# Main.net
KiCad netlist of a schematic drawn in Altium Designer
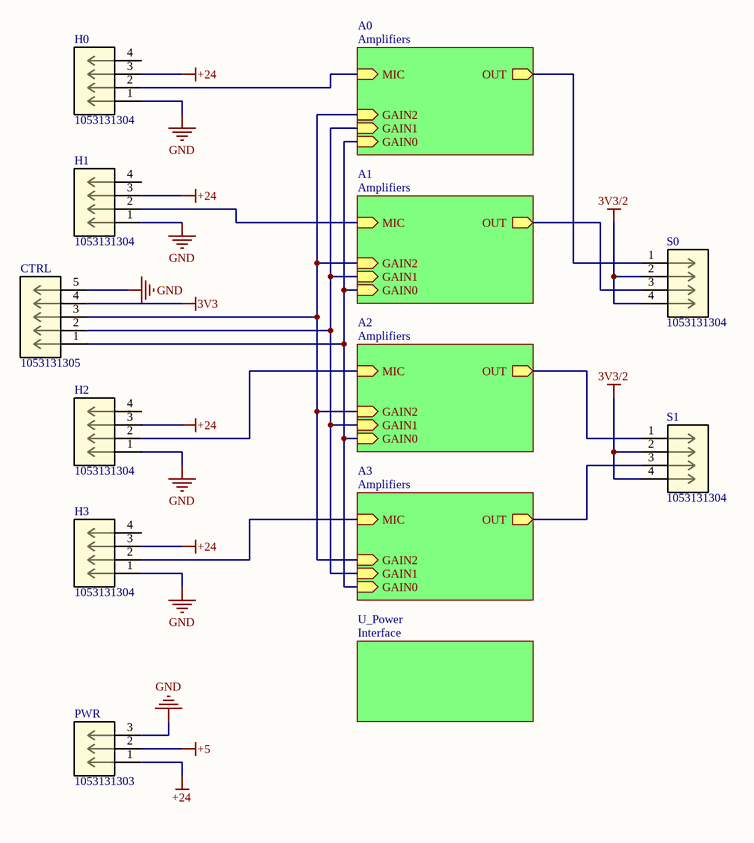
[diagram p0: Main.SchDoc]

(export (version "E")
  (design (tool "Eeschema 10.0.6"))
  (components
    (comp (ref "CTRL")
      (value "1053131305")
      (footprint "CON_1053131305")
      (description "No Description Available")
      (fields (field (name "COPYRIGHT") "Copyright (C) 2023 Ultra Librarian. All rights reserved."))
      (libsource (lib "1053131305") (part "1053131305"))
    )
    (comp (ref "H0")
      (value "1053131304")
      (footprint "CON_1053131304")
      (description "No Description Available")
      (fields (field (name "COPYRIGHT") "Copyright (C) 2023 Ultra Librarian. All rights reserved."))
      (libsource (lib "") (part "1053131304_1"))
    )
    (comp (ref "H1")
      (value "1053131304")
      (footprint "CON_1053131304")
      (description "No Description Available")
      (fields (field (name "COPYRIGHT") "Copyright (C) 2023 Ultra Librarian. All rights reserved."))
      (libsource (lib "") (part "1053131304_1"))
    )
    (comp (ref "H2")
      (value "1053131304")
      (footprint "CON_1053131304")
      (description "No Description Available")
      (fields (field (name "COPYRIGHT") "Copyright (C) 2023 Ultra Librarian. All rights reserved."))
      (libsource (lib "") (part "1053131304_1"))
    )
    (comp (ref "H3")
      (value "1053131304")
      (footprint "CON_1053131304")
      (description "No Description Available")
      (fields (field (name "COPYRIGHT") "Copyright (C) 2023 Ultra Librarian. All rights reserved."))
      (libsource (lib "") (part "1053131304_1"))
    )
    (comp (ref "PWR")
      (value "1053131303")
      (footprint "CON_1053131303")
      (description "No Description Available")
      (fields (field (name "COPYRIGHT") "Copyright (C) 2023 Ultra Librarian. All rights reserved."))
      (libsource (lib "1053131303") (part "1053131303"))
    )
    (comp (ref "S0")
      (value "1053131304")
      (footprint "CON_1053131304")
      (description "No Description Available")
      (fields (field (name "COPYRIGHT") "Copyright (C) 2023 Ultra Librarian. All rights reserved."))
      (libsource (lib "1053131304") (part "1053131304"))
    )
    (comp (ref "S1")
      (value "1053131304")
      (footprint "CON_1053131304")
      (description "No Description Available")
      (fields (field (name "COPYRIGHT") "Copyright (C) 2023 Ultra Librarian. All rights reserved."))
      (libsource (lib "1053131304") (part "1053131304"))
    )
  )
  (nets
    (net (code "1") (name "+5") (class "Default")
      (node (ref "PWR") (pin "2") (pinfunction "2_2") (pintype "passive"))
    )
    (net (code "2") (name "+24") (class "Default")
      (node (ref "H0") (pin "3") (pinfunction "3_3") (pintype "passive"))
      (node (ref "H1") (pin "3") (pinfunction "3_3") (pintype "passive"))
      (node (ref "H2") (pin "3") (pinfunction "3_3") (pintype "passive"))
      (node (ref "H3") (pin "3") (pinfunction "3_3") (pintype "passive"))
      (node (ref "PWR") (pin "1") (pinfunction "1_1") (pintype "passive"))
    )
    (net (code "3") (name "/GAIN0") (class "Default")
      (node (ref "CTRL") (pin "1") (pinfunction "1_1") (pintype "passive"))
    )
    (net (code "4") (name "/GAIN1") (class "Default")
      (node (ref "CTRL") (pin "2") (pinfunction "2_2") (pintype "passive"))
    )
    (net (code "5") (name "/GAIN2") (class "Default")
      (node (ref "CTRL") (pin "3") (pinfunction "3_3") (pintype "passive"))
    )
    (net (code "6") (name "/MIC") (class "Default")
      (node (ref "H2") (pin "2") (pinfunction "2_2") (pintype "passive"))
    )
    (net (code "7") (name "/MIC_1") (class "Default")
      (node (ref "H0") (pin "2") (pinfunction "2_2") (pintype "passive"))
    )
    (net (code "8") (name "/MIC_2") (class "Default")
      (node (ref "H1") (pin "2") (pinfunction "2_2") (pintype "passive"))
    )
    (net (code "9") (name "/MIC_3") (class "Default")
      (node (ref "H3") (pin "2") (pinfunction "2_2") (pintype "passive"))
    )
    (net (code "10") (name "/OUT") (class "Default")
      (node (ref "S1") (pin "1") (pinfunction "1_1") (pintype "passive"))
    )
    (net (code "11") (name "/OUT_1") (class "Default")
      (node (ref "S0") (pin "3") (pinfunction "3_3") (pintype "passive"))
    )
    (net (code "12") (name "/OUT_2") (class "Default")
      (node (ref "S0") (pin "1") (pinfunction "1_1") (pintype "passive"))
    )
    (net (code "13") (name "/OUT_3") (class "Default")
      (node (ref "S1") (pin "3") (pinfunction "3_3") (pintype "passive"))
    )
    (net (code "14") (name "3V3") (class "Default")
      (node (ref "CTRL") (pin "4") (pinfunction "4_4") (pintype "passive"))
    )
    (net (code "15") (name "3V3{slash}2") (class "Default")
      (node (ref "S0") (pin "2") (pinfunction "2_2") (pintype "passive"))
      (node (ref "S0") (pin "4") (pinfunction "4_4") (pintype "passive"))
      (node (ref "S1") (pin "2") (pinfunction "2_2") (pintype "passive"))
      (node (ref "S1") (pin "4") (pinfunction "4_4") (pintype "passive"))
    )
    (net (code "16") (name "GND") (class "Default")
      (node (ref "CTRL") (pin "5") (pinfunction "5_5") (pintype "passive"))
      (node (ref "H0") (pin "1") (pinfunction "1_1") (pintype "passive"))
      (node (ref "H1") (pin "1") (pinfunction "1_1") (pintype "passive"))
      (node (ref "H2") (pin "1") (pinfunction "1_1") (pintype "passive"))
      (node (ref "H3") (pin "1") (pinfunction "1_1") (pintype "passive"))
      (node (ref "PWR") (pin "3") (pinfunction "3_3") (pintype "passive"))
    )
    (net (code "17") (name "unconnected-(H0-Pad4)") (class "Default")
      (node (ref "H0") (pin "4") (pinfunction "4_4") (pintype "passive"))
    )
    (net (code "18") (name "unconnected-(H1-Pad4)") (class "Default")
      (node (ref "H1") (pin "4") (pinfunction "4_4") (pintype "passive"))
    )
    (net (code "19") (name "unconnected-(H2-Pad4)") (class "Default")
      (node (ref "H2") (pin "4") (pinfunction "4_4") (pintype "passive"))
    )
    (net (code "20") (name "unconnected-(H3-Pad4)") (class "Default")
      (node (ref "H3") (pin "4") (pinfunction "4_4") (pintype "passive"))
    )
  )
)
